# RTC.net
KiCad netlist of a schematic drawn in Altium Designer
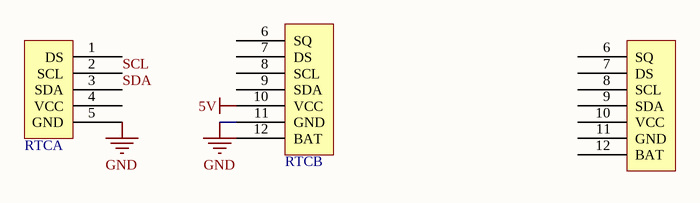
[diagram p0: RTC.SchDoc]

(export (version "E")
  (design (tool "Eeschema 10.0.6"))
  (components
    (comp (ref "RTC")
      (value "TinyRTC")
      (footprint "Tiny RTC")
      (description "Embase PCB, Carte-à-carte, 2.54 mm, 1 Rangée(s), 5 Contact(s), Montage traversant, SSW Series")
      (libsource (lib "MGLib_v2") (part "TinyRTC"))
    )
    (comp (ref "RTCB")
      (value "TinyRTC")
      (footprint "Tiny RTC")
      (description "Embase PCB, Carte-à-carte, 2.54 mm, 1 Rangée(s), 7 Contact(s), Montage traversant, SSW Series")
      (libsource (lib "MGLib_v2") (part "TinyRTC"))
    )
  )
  (nets
    (net (code "1") (name "/SCL") (class "Default")
      (node (ref "RTC") (pin "2") (pinfunction "SCL_2") (pintype "passive"))
    )
    (net (code "2") (name "/SDA") (class "Default")
      (node (ref "RTC") (pin "3") (pinfunction "SDA_3") (pintype "passive"))
    )
    (net (code "3") (name "5V") (class "Default")
      (node (ref "RTC") (pin "10") (pinfunction "VCC_10") (pintype "passive"))
    )
    (net (code "4") (name "GND") (class "Default")
      (node (ref "RTC") (pin "11") (pinfunction "GND_11") (pintype "passive"))
      (node (ref "RTC") (pin "5") (pinfunction "GND_5") (pintype "passive"))
    )
    (net (code "5") (name "unconnected-(RTCA-DS-Pad1)") (class "Default")
      (node (ref "RTC") (pin "1") (pinfunction "DS_1") (pintype "passive"))
    )
    (net (code "6") (name "unconnected-(RTCA-VCC-Pad4)") (class "Default")
      (node (ref "RTC") (pin "4") (pinfunction "VCC_4") (pintype "passive"))
    )
    (net (code "7") (name "unconnected-(RTCB-BAT-Pad12)") (class "Default")
      (node (ref "RTC") (pin "12") (pinfunction "BAT_12") (pintype "passive"))
    )
    (net (code "8") (name "unconnected-(RTCB-DS-Pad7)") (class "Default")
      (node (ref "RTC") (pin "7") (pinfunction "DS_7") (pintype "passive"))
    )
    (net (code "9") (name "unconnected-(RTCB-SCL-Pad8)") (class "Default")
      (node (ref "RTC") (pin "8") (pinfunction "SCL_8") (pintype "passive"))
    )
    (net (code "10") (name "unconnected-(RTCB-SDA-Pad9)") (class "Default")
      (node (ref "RTC") (pin "9") (pinfunction "SDA_9") (pintype "passive"))
    )
    (net (code "11") (name "unconnected-(RTCB-SQ-Pad6)") (class "Default")
      (node (ref "RTC") (pin "6") (pinfunction "SQ_6") (pintype "passive"))
    )
    (net (code "12") (name "unconnected-(RTCBB-BAT-Pad12)") (class "Default")
      (node (ref "RTCB") (pin "12") (pinfunction "BAT_12") (pintype "passive"))
    )
    (net (code "13") (name "unconnected-(RTCBB-DS-Pad7)") (class "Default")
      (node (ref "RTCB") (pin "7") (pinfunction "DS_7") (pintype "passive"))
    )
    (net (code "14") (name "unconnected-(RTCBB-GND-Pad11)") (class "Default")
      (node (ref "RTCB") (pin "11") (pinfunction "GND_11") (pintype "passive"))
    )
    (net (code "15") (name "unconnected-(RTCBB-SCL-Pad8)") (class "Default")
      (node (ref "RTCB") (pin "8") (pinfunction "SCL_8") (pintype "passive"))
    )
    (net (code "16") (name "unconnected-(RTCBB-SDA-Pad9)") (class "Default")
      (node (ref "RTCB") (pin "9") (pinfunction "SDA_9") (pintype "passive"))
    )
    (net (code "17") (name "unconnected-(RTCBB-SQ-Pad6)") (class "Default")
      (node (ref "RTCB") (pin "6") (pinfunction "SQ_6") (pintype "passive"))
    )
    (net (code "18") (name "unconnected-(RTCBB-VCC-Pad10)") (class "Default")
      (node (ref "RTCB") (pin "10") (pinfunction "VCC_10") (pintype "passive"))
    )
  )
)
